# 425AK01A_S04.net
KiCad netlist of a schematic drawn in Altium Designer
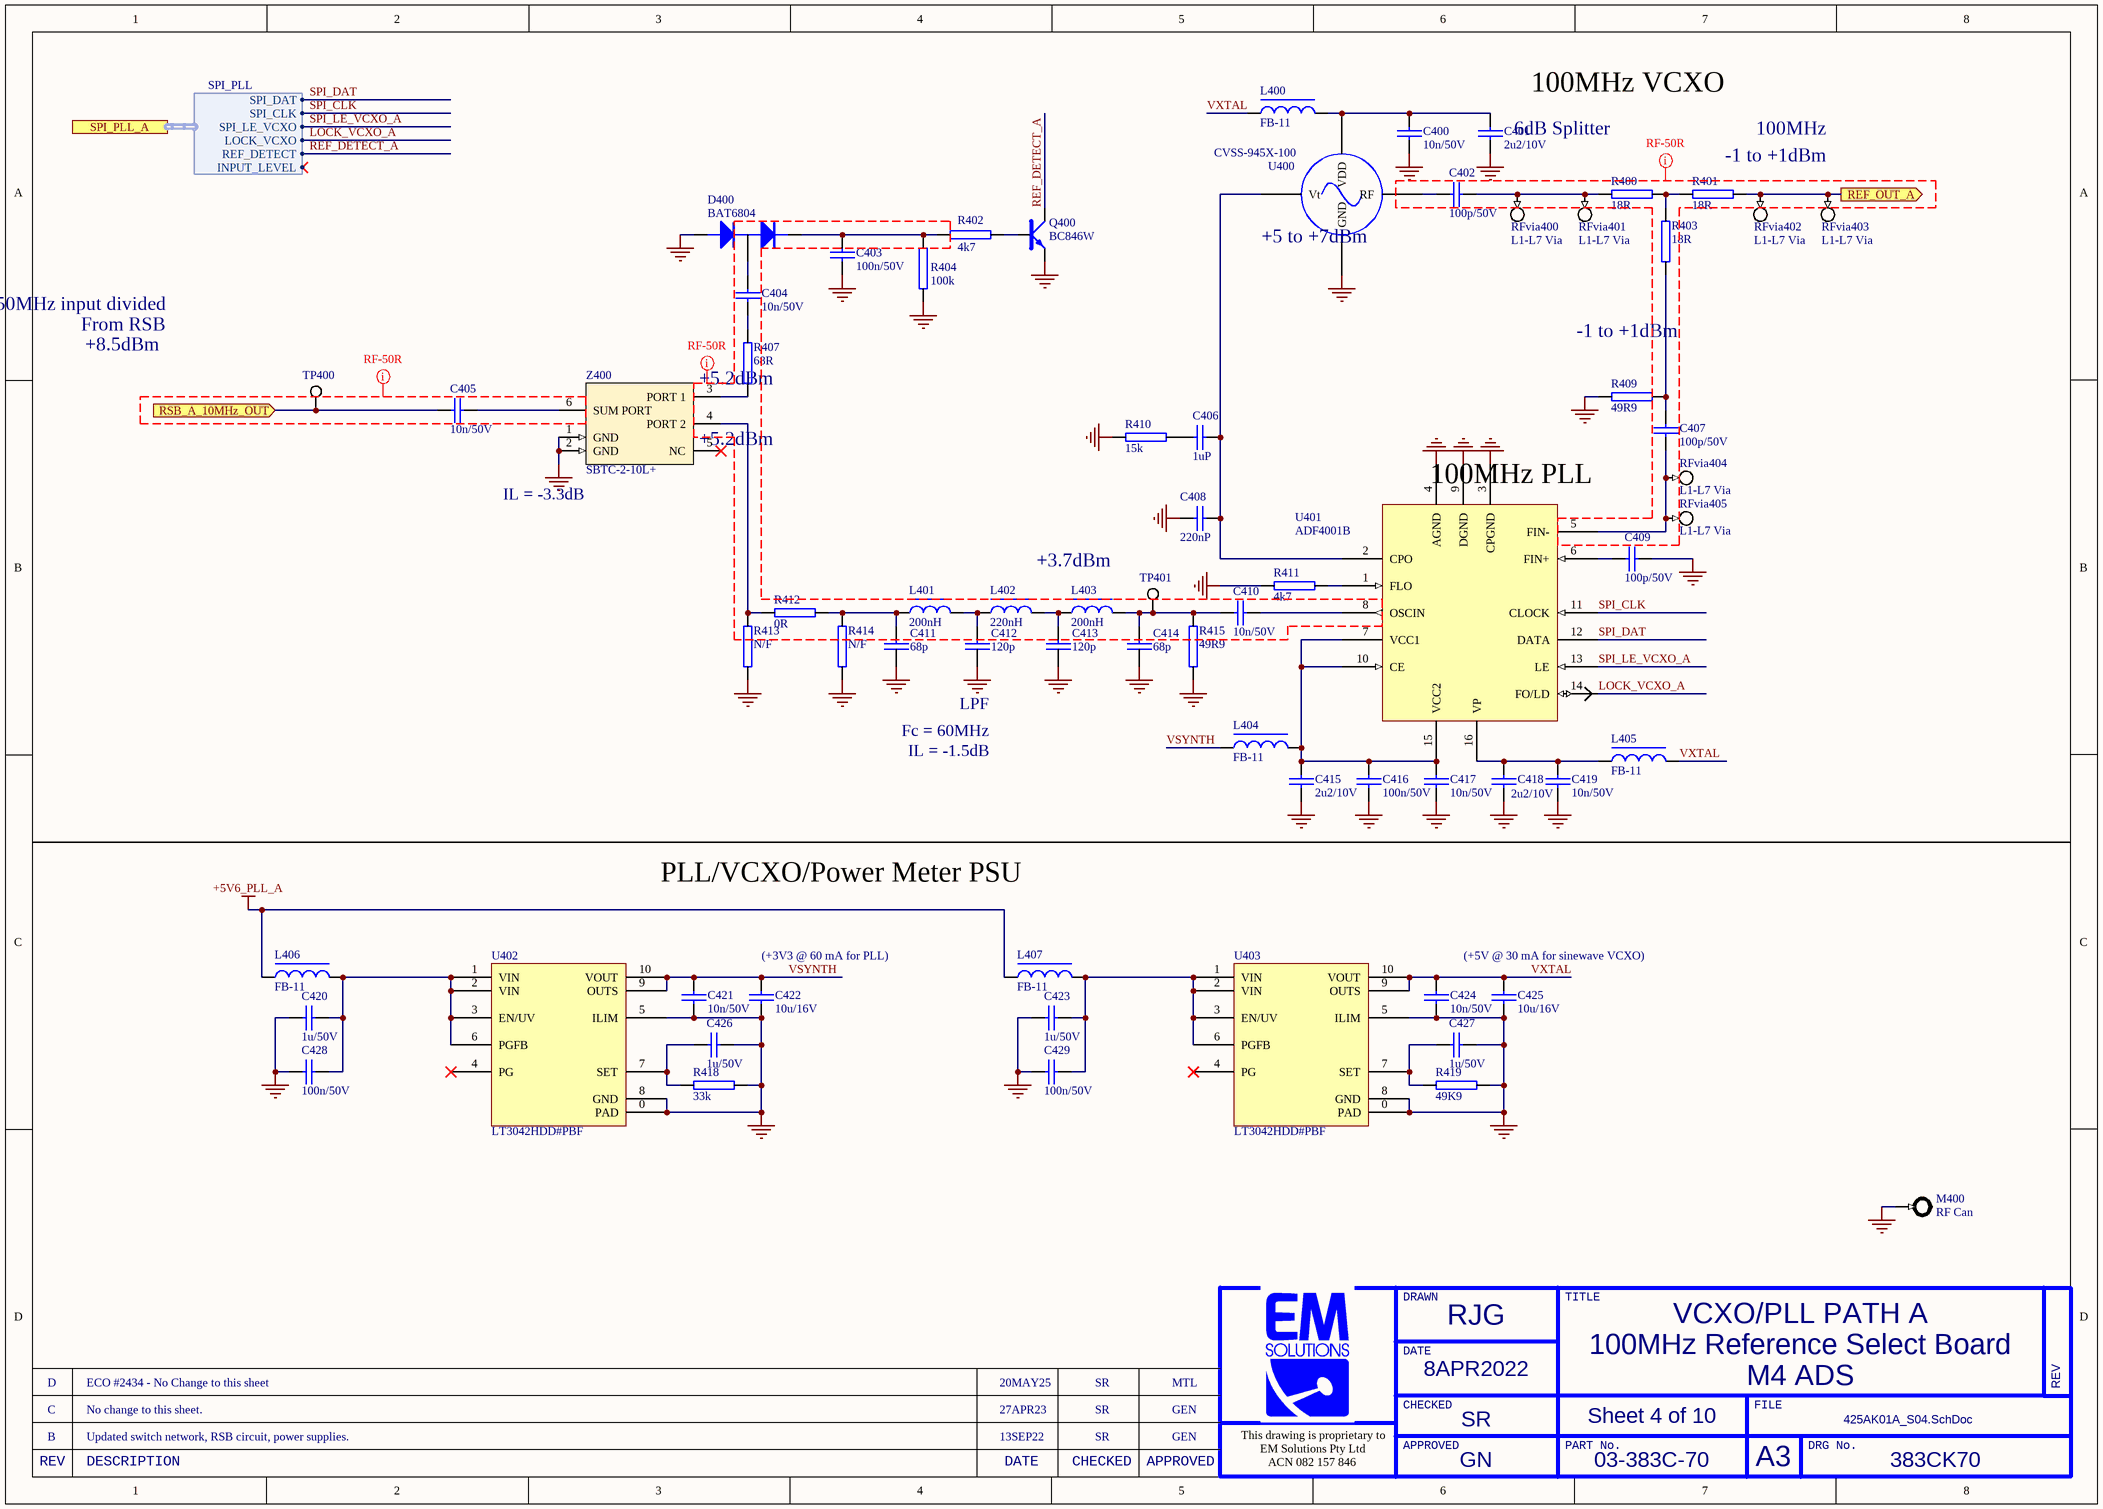
[diagram p0: 425AK01A_S04.SchDoc]

(export (version "E")
  (design (tool "Eeschema 10.0.6"))
  (components
    (comp (ref "C400")
      (value "10n/50V")
      (footprint "0402C")
      (description "Capacitor, 0402, 10n X7R 10% 50V Ceramic, NiSn")
      (fields (field (name "PART NUMBER") "41-010N-12") (field (name "MANUFACTURER") "MURATA"))
      (libsource (lib "EM DFM Library") (part "CAP"))
    )
    (comp (ref "C401")
      (value "2u2/10V")
      (footprint "0603C")
      (description "Capacitor, 0603, 2u2 X7R 10% 10V Ceramic, NiSn")
      (fields (field (name "PART NUMBER") "41-02U2-06") (field (name "MANUFACTURER") "MURATA"))
      (libsource (lib "EM DFM Library") (part "CAP"))
    )
    (comp (ref "C402")
      (value "100p/50V")
      (footprint "0402C")
      (description "Capacitor, 0402, 100p NPO 5% 50V Ceramic, AEC-Q200")
      (fields (field (name "PART NUMBER") "41-100P-11") (field (name "MANUFACTURER") "TDK"))
      (libsource (lib "EM DFM Library") (part "CAP"))
    )
    (comp (ref "C403")
      (value "100n/50V")
      (footprint "0402C")
      (description "Capacitor, 0402, 100n, X7R, 10% 50V, Ceramic")
      (fields (field (name "PART NUMBER") "41-100N-13") (field (name "MANUFACTURER") "MURATA"))
      (libsource (lib "EM DFM Library") (part "CAP"))
    )
    (comp (ref "C404")
      (value "10n/50V")
      (footprint "0402C")
      (description "Capacitor, 0402, 10n X7R 10% 50V Ceramic, NiSn")
      (fields (field (name "PART NUMBER") "41-010N-12") (field (name "MANUFACTURER") "MURATA"))
      (libsource (lib "EM DFM Library") (part "CAP"))
    )
    (comp (ref "C405")
      (value "10n/50V")
      (footprint "0402C")
      (description "Capacitor, 0402, 10n X7R 10% 50V Ceramic, NiSn")
      (fields (field (name "PART NUMBER") "41-010N-12") (field (name "MANUFACTURER") "MURATA"))
      (libsource (lib "EM DFM Library") (part "CAP"))
    )
    (comp (ref "C406")
      (value "1uP")
      (footprint "1210C")
      (description "Capacitor, 1210, 1u PPS 20% 16V Plastic Film")
      (fields (field (name "PART NUMBER") "41-01U0-05") (field (name "MANUFACTURER") "PANASONIC"))
      (libsource (lib "EM DFM Library") (part "CAP"))
    )
    (comp (ref "C407")
      (value "100p/50V")
      (footprint "0402C")
      (description "Capacitor, 0402, 100p NPO 5% 50V Ceramic, AEC-Q200")
      (fields (field (name "PART NUMBER") "41-100P-11") (field (name "MANUFACTURER") "TDK"))
      (libsource (lib "EM DFM Library") (part "CAP"))
    )
    (comp (ref "C408")
      (value "220nP")
      (footprint "1206C")
      (description "Capacitor, 1206, 220n PPS 20% 16V Plastic Film")
      (fields (field (name "PART NUMBER") "41-220N-05") (field (name "MANUFACTURER") "PANASONIC"))
      (libsource (lib "EM DFM Library") (part "CAP"))
    )
    (comp (ref "C409")
      (value "100p/50V")
      (footprint "0402C")
      (description "Capacitor, 0402, 100p NPO 5% 50V Ceramic, AEC-Q200")
      (fields (field (name "PART NUMBER") "41-100P-11") (field (name "MANUFACTURER") "TDK"))
      (libsource (lib "EM DFM Library") (part "CAP"))
    )
    (comp (ref "C410")
      (value "10n/50V")
      (footprint "0402C")
      (description "Capacitor, 0402, 10n X7R 10% 50V Ceramic, NiSn")
      (fields (field (name "PART NUMBER") "41-010N-12") (field (name "MANUFACTURER") "MURATA"))
      (libsource (lib "EM DFM Library") (part "CAP"))
    )
    (comp (ref "C411")
      (value "68p")
      (footprint "0402C")
      (description "Capacitor, 0402, 68p")
      (fields (field (name "PART NUMBER") "41-068P-08"))
      (libsource (lib "Russell") (part "41-068P-08"))
    )
    (comp (ref "C412")
      (value "120p")
      (footprint "0402C")
      (description "Capacitor, 0402, 120p NPO")
      (fields (field (name "PART NUMBER") "41-120P-05"))
      (libsource (lib "Russell") (part "41-120P-05"))
    )
    (comp (ref "C413")
      (value "120p")
      (footprint "0402C")
      (description "Capacitor, 0402, 120p NPO")
      (fields (field (name "PART NUMBER") "41-120P-05"))
      (libsource (lib "Russell") (part "41-120P-05"))
    )
    (comp (ref "C414")
      (value "68p")
      (footprint "0402C")
      (description "Capacitor, 0402, 68p")
      (fields (field (name "PART NUMBER") "41-068P-08"))
      (libsource (lib "Russell") (part "41-068P-08"))
    )
    (comp (ref "C415")
      (value "2u2/10V")
      (footprint "0603C")
      (description "Capacitor, 0603, 2u2 X7R 10% 10V Ceramic, NiSn")
      (fields (field (name "PART NUMBER") "41-02U2-06") (field (name "MANUFACTURER") "MURATA"))
      (libsource (lib "EM DFM Library") (part "CAP"))
    )
    (comp (ref "C416")
      (value "100n/50V")
      (footprint "0402C")
      (description "Capacitor, 0402, 100n, X7R, 10% 50V, Ceramic")
      (fields (field (name "PART NUMBER") "41-100N-13") (field (name "MANUFACTURER") "MURATA"))
      (libsource (lib "EM DFM Library") (part "CAP"))
    )
    (comp (ref "C417")
      (value "10n/50V")
      (footprint "0402C")
      (description "Capacitor, 0402, 10n X7R 10% 50V Ceramic, NiSn")
      (fields (field (name "PART NUMBER") "41-010N-12") (field (name "MANUFACTURER") "MURATA"))
      (libsource (lib "EM DFM Library") (part "CAP"))
    )
    (comp (ref "C418")
      (value "2u2/10V")
      (footprint "0603C")
      (description "Capacitor, 0603, 2u2 X7R 10% 10V Ceramic, NiSn")
      (fields (field (name "PART NUMBER") "41-02U2-06") (field (name "MANUFACTURER") "MURATA"))
      (libsource (lib "EM DFM Library") (part "CAP"))
    )
    (comp (ref "C419")
      (value "10n/50V")
      (footprint "0402C")
      (description "Capacitor, 0402, 10n X7R 10% 50V Ceramic, NiSn")
      (fields (field (name "PART NUMBER") "41-010N-12") (field (name "MANUFACTURER") "MURATA"))
      (libsource (lib "EM DFM Library") (part "CAP"))
    )
    (comp (ref "C420")
      (value "1u/50V")
      (footprint "0603C")
      (description "Capacitor, 0603, 1u X7R 10% 50V Ceramic, NiSn")
      (fields (field (name "PART NUMBER") "41-01U0-06") (field (name "MANUFACTURER") "TAIYOYUDEN"))
      (libsource (lib "EM DFM Library") (part "CAP"))
    )
    (comp (ref "C421")
      (value "10n/50V")
      (footprint "0402C")
      (description "Capacitor, 0402, 10n X7R 10% 50V Ceramic, NiSn")
      (fields (field (name "PART NUMBER") "41-010N-12") (field (name "MANUFACTURER") "MURATA"))
      (libsource (lib "EM DFM Library") (part "CAP"))
    )
    (comp (ref "C422")
      (value "10u/16V")
      (footprint "0805C")
      (description "Capacitor, 0805, 10u X7R 10% 16V Ceramic, NiSn")
      (fields (field (name "PART NUMBER") "41-010U-08") (field (name "MANUFACTURER") "SAMSUNG"))
      (libsource (lib "EM DFM Library") (part "CAP"))
    )
    (comp (ref "C423")
      (value "1u/50V")
      (footprint "0603C")
      (description "Capacitor, 0603, 1u X7R 10% 50V Ceramic, NiSn")
      (fields (field (name "PART NUMBER") "41-01U0-06") (field (name "MANUFACTURER") "TAIYOYUDEN"))
      (libsource (lib "EM DFM Library") (part "CAP"))
    )
    (comp (ref "C424")
      (value "10n/50V")
      (footprint "0402C")
      (description "Capacitor, 0402, 10n X7R 10% 50V Ceramic, NiSn")
      (fields (field (name "PART NUMBER") "41-010N-12") (field (name "MANUFACTURER") "MURATA"))
      (libsource (lib "EM DFM Library") (part "CAP"))
    )
    (comp (ref "C425")
      (value "10u/16V")
      (footprint "0805C")
      (description "Capacitor, 0805, 10u X7R 10% 16V Ceramic, NiSn")
      (fields (field (name "PART NUMBER") "41-010U-08") (field (name "MANUFACTURER") "SAMSUNG"))
      (libsource (lib "EM DFM Library") (part "CAP"))
    )
    (comp (ref "C426")
      (value "1u/50V")
      (footprint "0603C")
      (description "Capacitor, 0603, 1u X7R 10% 50V Ceramic, NiSn")
      (fields (field (name "PART NUMBER") "41-01U0-06") (field (name "MANUFACTURER") "TAIYOYUDEN"))
      (libsource (lib "EM DFM Library") (part "CAP"))
    )
    (comp (ref "C427")
      (value "1u/50V")
      (footprint "0603C")
      (description "Capacitor, 0603, 1u X7R 10% 50V Ceramic, NiSn")
      (fields (field (name "PART NUMBER") "41-01U0-06") (field (name "MANUFACTURER") "TAIYOYUDEN"))
      (libsource (lib "EM DFM Library") (part "CAP"))
    )
    (comp (ref "C428")
      (value "100n/50V")
      (footprint "0402C")
      (description "Capacitor, 0402, 100n, X7R, 10% 50V, Ceramic")
      (fields (field (name "PART NUMBER") "41-100N-13") (field (name "MANUFACTURER") "MURATA"))
      (libsource (lib "EM DFM Library") (part "CAP"))
    )
    (comp (ref "C429")
      (value "100n/50V")
      (footprint "0402C")
      (description "Capacitor, 0402, 100n, X7R, 10% 50V, Ceramic")
      (fields (field (name "PART NUMBER") "41-100N-13") (field (name "MANUFACTURER") "MURATA"))
      (libsource (lib "EM DFM Library") (part "CAP"))
    )
    (comp (ref "D400")
      (value "BAT6804")
      (footprint "SOT-23DAP")
      (description "*Diode, Schottky, Series Pair, 8V 130mA, SOT-23-3")
      (fields (field (name "PART NUMBER") "60-BAT68-04") (field (name "MANUFACTURER") "INFINEON"))
      (libsource (lib "EM DFM Library") (part "DIODE_AP2"))
    )
    (comp (ref "L400")
      (value "FB-11")
      (footprint "0402L")
      (description "Solid Inductor, 600ohm@100MHz, DCR=0.52, 0.3A, 0402 size")
      (fields (field (name "PART NUMBER") "46-B-11") (field (name "MANUFACTURER") "TDK"))
      (libsource (lib "EM DFM Library") (part "IND"))
    )
    (comp (ref "L401")
      (value "200nH")
      (footprint "0402L")
      (description "Inductor, Chip, 200nH, 0402")
      (fields (field (name "PART NUMBER") "46-200N-04"))
      (libsource (lib "Russell") (part "46-200N-04"))
    )
    (comp (ref "L402")
      (value "220nH")
      (footprint "0402L")
      (description "Inductor, Chip, 220nH, 0402")
      (fields (field (name "PART NUMBER") "46-220N-05"))
      (libsource (lib "Russell") (part "46-220N-05"))
    )
    (comp (ref "L403")
      (value "200nH")
      (footprint "0402L")
      (description "Inductor, Chip, 200nH, 0402")
      (fields (field (name "PART NUMBER") "46-200N-04"))
      (libsource (lib "Russell") (part "46-200N-04"))
    )
    (comp (ref "L404")
      (value "FB-11")
      (footprint "0402L")
      (description "Solid Inductor, 600ohm@100MHz, DCR=0.52, 0.3A, 0402 size")
      (fields (field (name "PART NUMBER") "46-B-11") (field (name "MANUFACTURER") "TDK"))
      (libsource (lib "EM DFM Library") (part "IND"))
    )
    (comp (ref "L405")
      (value "FB-11")
      (footprint "0402L")
      (description "Solid Inductor, 600ohm@100MHz, DCR=0.52, 0.3A, 0402 size")
      (fields (field (name "PART NUMBER") "46-B-11") (field (name "MANUFACTURER") "TDK"))
      (libsource (lib "EM DFM Library") (part "IND"))
    )
    (comp (ref "L406")
      (value "FB-11")
      (footprint "0402L")
      (description "Solid Inductor, 600ohm@100MHz, DCR=0.52, 0.3A, 0402 size")
      (fields (field (name "PART NUMBER") "46-B-11") (field (name "MANUFACTURER") "TDK"))
      (libsource (lib "") (part "IND_1"))
    )
    (comp (ref "L407")
      (value "FB-11")
      (footprint "0402L")
      (description "Solid Inductor, 600ohm@100MHz, DCR=0.52, 0.3A, 0402 size")
      (fields (field (name "PART NUMBER") "46-B-11") (field (name "MANUFACTURER") "TDK"))
      (libsource (lib "") (part "IND_1"))
    )
    (comp (ref "M400")
      (value "RF Can")
      (footprint "Can_38x25.4x6mm")
      (fields (field (name "PART NUMBER") "11-0256"))
      (libsource (lib "Russell") (part "Can-RF"))
    )
    (comp (ref "Q400")
      (value "BC846W")
      (footprint "SOT-323BJT")
      (description "Transistor, NPN Si, GenPur 65V 100mA, SOT-323")
      (fields (field (name "PART NUMBER") "62-BC846-01") (field (name "MANUFACTURER") "TAIWAN SEMI"))
      (libsource (lib "EM DFM Library") (part "NPN"))
    )
    (comp (ref "R400")
      (value "18R")
      (footprint "0402")
      (description "Resistor, 0402, 18R 1% 0.063W")
      (fields (field (name "PART NUMBER") "44-018R-10") (field (name "MANUFACTURER") "GENERIC"))
      (libsource (lib "EM DFM Library") (part "RES"))
    )
    (comp (ref "R401")
      (value "18R")
      (footprint "0402")
      (description "Resistor, 0402, 18R 1% 0.063W")
      (fields (field (name "PART NUMBER") "44-018R-10") (field (name "MANUFACTURER") "GENERIC"))
      (libsource (lib "EM DFM Library") (part "RES"))
    )
    (comp (ref "R402")
      (value "4k7")
      (footprint "0402")
      (description "Resistor, 0402, 4k7 1% 0.063W")
      (fields (field (name "PART NUMBER") "44-04K7-10") (field (name "MANUFACTURER") "PHILIPS"))
      (libsource (lib "EM DFM Library") (part "RES"))
    )
    (comp (ref "R403")
      (value "18R")
      (footprint "0402")
      (description "Resistor, 0402, 18R 1% 0.063W")
      (fields (field (name "PART NUMBER") "44-018R-10") (field (name "MANUFACTURER") "GENERIC"))
      (libsource (lib "EM DFM Library") (part "RES"))
    )
    (comp (ref "R404")
      (value "100k")
      (footprint "0402")
      (description "Resistor, 0402, 100k 1% 0.063W")
      (fields (field (name "PART NUMBER") "44-100K-10") (field (name "MANUFACTURER") "PHILIPS"))
      (libsource (lib "EM DFM Library") (part "RES"))
    )
    (comp (ref "R407")
      (value "68R")
      (footprint "0402")
      (description "Resistor, 0402, 68R 1% 0.063W")
      (fields (field (name "PART NUMBER") "44-068R-10") (field (name "MANUFACTURER") "PHILIPS"))
      (libsource (lib "EM DFM Library") (part "RES"))
    )
    (comp (ref "R409")
      (value "49R9")
      (footprint "0402")
      (description "Resistor, 0402, 49R9 1% 0.063W")
      (fields (field (name "PART NUMBER") "44-049R9-10") (field (name "MANUFACTURER") "YAGEO"))
      (libsource (lib "EM DFM Library") (part "RES"))
    )
    (comp (ref "R410")
      (value "15k")
      (footprint "0402")
      (description "Resistor, 0402, 15k 1% 0.063W")
      (fields (field (name "PART NUMBER") "44-015K-10") (field (name "MANUFACTURER") "PHILIPS"))
      (libsource (lib "EM DFM Library") (part "RES"))
    )
    (comp (ref "R411")
      (value "4k7")
      (footprint "0402")
      (description "Resistor, 0402, 4k7 1% 0.063W")
      (fields (field (name "PART NUMBER") "44-04K7-10") (field (name "MANUFACTURER") "PHILIPS"))
      (libsource (lib "EM DFM Library") (part "RES"))
    )
    (comp (ref "R412")
      (value "0R")
      (footprint "0402")
      (description "Resistor, 0402, 0R 1% 0.063W")
      (fields (field (name "PART NUMBER") "44-000R-10") (field (name "MANUFACTURER") "GENERIC"))
      (libsource (lib "EM DFM Library") (part "RES"))
    )
    (comp (ref "R413")
      (value "N/F")
      (footprint "0402")
      (description "Resistor, 0402, SOT, Not Fitted")
      (fields (field (name "PART NUMBER") "44-N/F-10"))
      (libsource (lib "EM DFM Library") (part "RES"))
    )
    (comp (ref "R414")
      (value "N/F")
      (footprint "0402")
      (description "Resistor, 0402, SOT, Not Fitted")
      (fields (field (name "PART NUMBER") "44-N/F-10"))
      (libsource (lib "EM DFM Library") (part "RES"))
    )
    (comp (ref "R415")
      (value "49R9")
      (footprint "0402")
      (description "Resistor, 0402, 49R9 1% 0.063W")
      (fields (field (name "PART NUMBER") "44-049R9-10") (field (name "MANUFACTURER") "YAGEO"))
      (libsource (lib "EM DFM Library") (part "RES"))
    )
    (comp (ref "R418")
      (value "33k")
      (footprint "0402")
      (description "Resistor, 0402, 33k 1% 0.063W")
      (fields (field (name "PART NUMBER") "44-033K-10") (field (name "MANUFACTURER") "PHILIPS"))
      (libsource (lib "EM DFM Library") (part "RES"))
    )
    (comp (ref "R419")
      (value "49K9")
      (footprint "0402")
      (description "Resistor, 0402, 49.9K, 1%, 0.1W, ThickFilm, AEC-Q200")
      (fields (field (name "PART NUMBER") "44-49K9-01") (field (name "MANUFACTURER") "PANASONIC"))
      (libsource (lib "EM DFM Library") (part "RES"))
    )
    (comp (ref "RFvia400")
      (value "L1-L7 Via")
      (footprint "RFvia_L1-L7")
      (description "RF Via from layer 1 to layer 7, on an 8-layer board.")
      (libsource (lib "RFvias-8layer") (part "RFvia_L1-L7"))
    )
    (comp (ref "RFvia401")
      (value "L1-L7 Via")
      (footprint "RFvia_L1-L7")
      (description "RF Via from layer 1 to layer 7, on an 8-layer board.")
      (libsource (lib "RFvias-8layer") (part "RFvia_L1-L7"))
    )
    (comp (ref "RFvia402")
      (value "L1-L7 Via")
      (footprint "RFvia_L1-L7")
      (description "RF Via from layer 1 to layer 7, on an 8-layer board.")
      (libsource (lib "RFvias-8layer") (part "RFvia_L1-L7"))
    )
    (comp (ref "RFvia403")
      (value "L1-L7 Via")
      (footprint "RFvia_L1-L7")
      (description "RF Via from layer 1 to layer 7, on an 8-layer board.")
      (libsource (lib "RFvias-8layer") (part "RFvia_L1-L7"))
    )
    (comp (ref "RFvia404")
      (value "L1-L7 Via")
      (footprint "RFvia_L1-L7")
      (description "RF Via from layer 1 to layer 7, on an 8-layer board.")
      (libsource (lib "RFvias-8layer") (part "RFvia_L1-L7"))
    )
    (comp (ref "RFvia405")
      (value "L1-L7 Via")
      (footprint "RFvia_L1-L7")
      (description "RF Via from layer 1 to layer 7, on an 8-layer board.")
      (libsource (lib "RFvias-8layer") (part "RFvia_L1-L7"))
    )
    (comp (ref "TP400")
      (value "Pad")
      (footprint "Testpoint-0.5mm-SMT-withPaste")
      (description "Pad that can be a test point or a hot via")
      (libsource (lib "Russell") (part "Pad"))
    )
    (comp (ref "TP401")
      (value "Pad")
      (footprint "Testpoint-0.5mm-SMT-withPaste")
      (description "Pad that can be a test point or a hot via")
      (libsource (lib "Russell") (part "Pad"))
    )
    (comp (ref "U400")
      (value "CVSS-945X-100")
      (footprint "CVHD-950")
      (description "VCXO, 100.00MHz, Sine 5V, SMD")
      (fields (field (name "PART NUMBER") "35-0223") (field (name "MANUFACTURER") "CRYSTEK"))
      (libsource (lib "EM DFM Library") (part "CVHD-950X-100"))
    )
    (comp (ref "U401")
      (value "ADF4001B")
      (footprint "TSSOP-16")
      (description "PLL Clock Gen, 200MHz, Serial TSSOP-16")
      (fields (field (name "PART NUMBER") "54-4001-01") (field (name "MANUFACTURER") "ANLG DEV"))
      (libsource (lib "EM DFM Library") (part "ADF4001BRUZ"))
    )
    (comp (ref "U402")
      (value "LT3042HDD#PBF")
      (footprint "DFN50P300X300X80_HS-11N")
      (description "Volt Regulator, Vin=1.8-20V, Vin=0-15V, 200mA, Low Noise, -40to+125C")
      (fields (field (name "PART NUMBER") "52-3042-01") (field (name "MANUFACTURER") "ANLG DEV"))
      (libsource (lib "EM DFM Library") (part "LT3042"))
    )
    (comp (ref "U403")
      (value "LT3042HDD#PBF")
      (footprint "DFN50P300X300X80_HS-11N")
      (description "Volt Regulator, Vin=1.8-20V, Vin=0-15V, 200mA, Low Noise, -40to+125C")
      (fields (field (name "PART NUMBER") "52-3042-01") (field (name "MANUFACTURER") "ANLG DEV"))
      (libsource (lib "EM DFM Library") (part "LT3042"))
    )
    (comp (ref "Z400")
      (value "SBTC-2-10L+")
      (footprint "SBTC-2-10L+")
      (description "Divider/Combiner, 2 Way, 0 deg, 10 -1000MHz, Tx Line Tranformer")
      (fields (field (name "PART NUMBER") "33-0055") (field (name "MANUFACTURER") "MINICCTS"))
      (libsource (lib "EM DFM Library") (part "SBTC-2-10L+"))
    )
  )
  (nets
    (net (code "2") (name "+5V6_PLL_A") (class "Default")
      (node (ref "L406") (pin "2") (pinfunction "2_2") (pintype "passive"))
      (node (ref "L407") (pin "2") (pinfunction "2_2") (pintype "passive"))
    )
    (net (code "3") (name "/LOCK_VCXO_A") (class "Default")
      (node (ref "U401") (pin "14") (pinfunction "FO/LD_14") (pintype "bidirectional"))
    )
    (net (code "4") (name "/REF_DETECT_A") (class "Default")
      (node (ref "Q400") (pin "C") (pinfunction "C_C") (pintype "passive"))
    )
    (net (code "5") (name "/REF_OUT_A") (class "Default")
      (node (ref "R401") (pin "2") (pintype "passive"))
      (node (ref "RFvia402") (pin "1") (pinfunction "1_1") (pintype "input"))
      (node (ref "RFvia403") (pin "1") (pinfunction "1_1") (pintype "input"))
    )
    (net (code "6") (name "/RSB_A_10MHz_OUT") (class "Default")
      (node (ref "C405") (pin "1") (pintype "passive"))
      (node (ref "TP400") (pin "1") (pinfunction "1_1") (pintype "passive"))
    )
    (net (code "7") (name "/SPI_CLK") (class "Default")
      (node (ref "U401") (pin "11") (pinfunction "CLOCK_11") (pintype "input"))
    )
    (net (code "8") (name "/SPI_DAT") (class "Default")
      (node (ref "U401") (pin "12") (pinfunction "DATA_12") (pintype "passive"))
    )
    (net (code "9") (name "/SPI_LE_VCXO_A") (class "Default")
      (node (ref "U401") (pin "13") (pinfunction "LE_13") (pintype "input"))
    )
    (net (code "10") (name "/VSYNTH") (class "Default")
      (node (ref "C421") (pin "2") (pintype "passive"))
      (node (ref "C422") (pin "1") (pintype "passive"))
      (node (ref "L404") (pin "1") (pinfunction "1_1") (pintype "passive"))
      (node (ref "U402") (pin "10") (pinfunction "VOUT_10") (pintype "passive"))
      (node (ref "U402") (pin "9") (pinfunction "OUTS_9") (pintype "passive"))
    )
    (net (code "11") (name "/VXTAL") (class "Default")
      (node (ref "C424") (pin "2") (pintype "passive"))
      (node (ref "C425") (pin "1") (pintype "passive"))
      (node (ref "L400") (pin "1") (pinfunction "1_1") (pintype "passive"))
      (node (ref "L405") (pin "2") (pinfunction "2_2") (pintype "passive"))
      (node (ref "U403") (pin "10") (pinfunction "VOUT_10") (pintype "passive"))
      (node (ref "U403") (pin "9") (pinfunction "OUTS_9") (pintype "passive"))
    )
    (net (code "13") (name "GND") (class "Default")
      (node (ref "C400") (pin "2") (pintype "passive"))
      (node (ref "C401") (pin "2") (pintype "passive"))
      (node (ref "C403") (pin "1") (pintype "passive"))
      (node (ref "C408") (pin "1") (pintype "passive"))
      (node (ref "C409") (pin "2") (pintype "passive"))
      (node (ref "C411") (pin "1") (pintype "passive"))
      (node (ref "C412") (pin "1") (pintype "passive"))
      (node (ref "C413") (pin "1") (pintype "passive"))
      (node (ref "C414") (pin "1") (pintype "passive"))
      (node (ref "C415") (pin "2") (pintype "passive"))
      (node (ref "C416") (pin "2") (pintype "passive"))
      (node (ref "C417") (pin "2") (pintype "passive"))
      (node (ref "C418") (pin "2") (pintype "passive"))
      (node (ref "C419") (pin "2") (pintype "passive"))
      (node (ref "C420") (pin "1") (pintype "passive"))
      (node (ref "C421") (pin "1") (pintype "passive"))
      (node (ref "C422") (pin "2") (pintype "passive"))
      (node (ref "C423") (pin "1") (pintype "passive"))
      (node (ref "C424") (pin "1") (pintype "passive"))
      (node (ref "C425") (pin "2") (pintype "passive"))
      (node (ref "C426") (pin "2") (pintype "passive"))
      (node (ref "C427") (pin "2") (pintype "passive"))
      (node (ref "C428") (pin "2") (pintype "passive"))
      (node (ref "C429") (pin "2") (pintype "passive"))
      (node (ref "D400") (pin "A") (pintype "passive"))
      (node (ref "M400") (pin "0") (pinfunction "0_0") (pintype "input"))
      (node (ref "Q400") (pin "E") (pinfunction "E_E") (pintype "passive"))
      (node (ref "R404") (pin "1") (pintype "passive"))
      (node (ref "R409") (pin "2") (pintype "passive"))
      (node (ref "R410") (pin "2") (pintype "passive"))
      (node (ref "R411") (pin "1") (pintype "passive"))
      (node (ref "R413") (pin "1") (pintype "passive"))
      (node (ref "R414") (pin "1") (pintype "passive"))
      (node (ref "R415") (pin "1") (pintype "passive"))
      (node (ref "R418") (pin "1") (pintype "passive"))
      (node (ref "R419") (pin "1") (pintype "passive"))
      (node (ref "U400") (pin "2") (pinfunction "GND_2") (pintype "passive"))
      (node (ref "U401") (pin "3") (pinfunction "CPGND_3") (pintype "passive"))
      (node (ref "U401") (pin "4") (pinfunction "AGND_4") (pintype "passive"))
      (node (ref "U401") (pin "9") (pinfunction "DGND_9") (pintype "passive"))
      (node (ref "U402") (pin "0") (pinfunction "PAD_0") (pintype "passive"))
      (node (ref "U402") (pin "5") (pinfunction "ILIM_5") (pintype "passive"))
      (node (ref "U402") (pin "8") (pinfunction "GND_8") (pintype "passive"))
      (node (ref "U403") (pin "0") (pinfunction "PAD_0") (pintype "passive"))
      (node (ref "U403") (pin "5") (pinfunction "ILIM_5") (pintype "passive"))
      (node (ref "U403") (pin "8") (pinfunction "GND_8") (pintype "passive"))
      (node (ref "Z400") (pin "1") (pinfunction "GND_1") (pintype "input"))
      (node (ref "Z400") (pin "2") (pinfunction "GND_2") (pintype "input"))
    )
    (net (code "14") (name "Net-(C402-Pad1)") (class "Default")
      (node (ref "C402") (pin "1") (pintype "passive"))
      (node (ref "R400") (pin "1") (pintype "passive"))
      (node (ref "RFvia400") (pin "1") (pinfunction "1_1") (pintype "input"))
      (node (ref "RFvia401") (pin "1") (pinfunction "1_1") (pintype "input"))
    )
    (net (code "15") (name "Net-(C403-Pad2)") (class "Default")
      (node (ref "C403") (pin "2") (pintype "passive"))
      (node (ref "D400") (pin "K") (pintype "passive"))
      (node (ref "R402") (pin "2") (pintype "passive"))
      (node (ref "R404") (pin "2") (pintype "passive"))
    )
    (net (code "16") (name "Net-(C404-Pad1)") (class "Default")
      (node (ref "C404") (pin "1") (pintype "passive"))
      (node (ref "R407") (pin "2") (pintype "passive"))
    )
    (net (code "17") (name "Net-(C404-Pad2)") (class "Default")
      (node (ref "C404") (pin "2") (pintype "passive"))
      (node (ref "D400") (pin "KA") (pintype "passive"))
    )
    (net (code "18") (name "Net-(C406-Pad2)") (class "Default")
      (node (ref "C406") (pin "2") (pintype "passive"))
      (node (ref "R410") (pin "1") (pintype "passive"))
    )
    (net (code "19") (name "Net-(C407-Pad1)") (class "Default")
      (node (ref "C407") (pin "1") (pintype "passive"))
      (node (ref "R403") (pin "2") (pintype "passive"))
      (node (ref "R409") (pin "1") (pintype "passive"))
    )
    (net (code "20") (name "Net-(C410-Pad1)") (class "Default")
      (node (ref "C410") (pin "1") (pintype "passive"))
      (node (ref "C414") (pin "2") (pintype "passive"))
      (node (ref "L403") (pin "2") (pinfunction "2_2") (pintype "passive"))
      (node (ref "R415") (pin "2") (pintype "passive"))
      (node (ref "TP401") (pin "1") (pinfunction "1_1") (pintype "passive"))
    )
    (net (code "21") (name "Net-(C411-Pad2)") (class "Default")
      (node (ref "C411") (pin "2") (pintype "passive"))
      (node (ref "L401") (pin "1") (pinfunction "1_1") (pintype "passive"))
      (node (ref "R412") (pin "1") (pintype "passive"))
      (node (ref "R414") (pin "2") (pintype "passive"))
    )
    (net (code "22") (name "Net-(C412-Pad2)") (class "Default")
      (node (ref "C412") (pin "2") (pintype "passive"))
      (node (ref "L401") (pin "2") (pinfunction "2_2") (pintype "passive"))
      (node (ref "L402") (pin "1") (pinfunction "1_1") (pintype "passive"))
    )
    (net (code "23") (name "Net-(C413-Pad2)") (class "Default")
      (node (ref "C413") (pin "2") (pintype "passive"))
      (node (ref "L402") (pin "2") (pinfunction "2_2") (pintype "passive"))
      (node (ref "L403") (pin "1") (pinfunction "1_1") (pintype "passive"))
    )
    (net (code "24") (name "Net-(Q400-PadB)") (class "Default")
      (node (ref "Q400") (pin "B") (pinfunction "B_B") (pintype "passive"))
      (node (ref "R402") (pin "1") (pintype "passive"))
    )
    (net (code "25") (name "Net-(R400-Pad2)") (class "Default")
      (node (ref "R400") (pin "2") (pintype "passive"))
      (node (ref "R401") (pin "1") (pintype "passive"))
      (node (ref "R403") (pin "1") (pintype "passive"))
    )
    (net (code "26") (name "Net-(U400-RF)") (class "Default")
      (node (ref "C402") (pin "2") (pintype "passive"))
      (node (ref "U400") (pin "3") (pinfunction "RF_3") (pintype "passive"))
    )
    (net (code "27") (name "Net-(U400-VDD)") (class "Default")
      (node (ref "C400") (pin "1") (pintype "passive"))
      (node (ref "C401") (pin "1") (pintype "passive"))
      (node (ref "L400") (pin "2") (pinfunction "2_2") (pintype "passive"))
      (node (ref "U400") (pin "4") (pinfunction "VDD_4") (pintype "passive"))
    )
    (net (code "28") (name "Net-(U400-Vt)") (class "Default")
      (node (ref "C406") (pin "1") (pintype "passive"))
      (node (ref "C408") (pin "2") (pintype "passive"))
      (node (ref "U400") (pin "1") (pinfunction "Vt_1") (pintype "passive"))
      (node (ref "U401") (pin "2") (pinfunction "CPO_2") (pintype "passive"))
    )
    (net (code "29") (name "Net-(U401-CE)") (class "Default")
      (node (ref "C415") (pin "1") (pintype "passive"))
      (node (ref "C416") (pin "1") (pintype "passive"))
      (node (ref "C417") (pin "1") (pintype "passive"))
      (node (ref "L404") (pin "2") (pinfunction "2_2") (pintype "passive"))
      (node (ref "U401") (pin "10") (pinfunction "CE_10") (pintype "input"))
      (node (ref "U401") (pin "15") (pinfunction "VCC2_15") (pintype "power_in"))
      (node (ref "U401") (pin "7") (pinfunction "VCC1_7") (pintype "power_in"))
    )
    (net (code "30") (name "Net-(U401-FIN+)") (class "Default")
      (node (ref "C409") (pin "1") (pintype "passive"))
      (node (ref "U401") (pin "6") (pinfunction "FIN+_6") (pintype "input"))
    )
    (net (code "31") (name "Net-(U401-FIN-)") (class "Default")
      (node (ref "C407") (pin "2") (pintype "passive"))
      (node (ref "RFvia404") (pin "1") (pinfunction "1_1") (pintype "input"))
      (node (ref "RFvia405") (pin "1") (pinfunction "1_1") (pintype "input"))
      (node (ref "U401") (pin "5") (pinfunction "FIN-_5") (pintype "power_in"))
    )
    (net (code "32") (name "Net-(U401-FLO)") (class "Default")
      (node (ref "R411") (pin "2") (pintype "passive"))
      (node (ref "U401") (pin "1") (pinfunction "FLO_1") (pintype "input"))
    )
    (net (code "33") (name "Net-(U401-OSCIN)") (class "Default")
      (node (ref "C410") (pin "2") (pintype "passive"))
      (node (ref "U401") (pin "8") (pinfunction "OSCIN_8") (pintype "output"))
    )
    (net (code "34") (name "Net-(U401-VP)") (class "Default")
      (node (ref "C418") (pin "1") (pintype "passive"))
      (node (ref "C419") (pin "1") (pintype "passive"))
      (node (ref "L405") (pin "1") (pinfunction "1_1") (pintype "passive"))
      (node (ref "U401") (pin "16") (pinfunction "VP_16") (pintype "power_in"))
    )
    (net (code "35") (name "Net-(U402-EN{slash}UV)") (class "Default")
      (node (ref "C420") (pin "2") (pintype "passive"))
      (node (ref "C428") (pin "1") (pintype "passive"))
      (node (ref "L406") (pin "1") (pinfunction "1_1") (pintype "passive"))
      (node (ref "U402") (pin "1") (pinfunction "VIN_1") (pintype "passive"))
      (node (ref "U402") (pin "2") (pinfunction "VIN_2") (pintype "passive"))
      (node (ref "U402") (pin "3") (pinfunction "EN/UV_3") (pintype "passive"))
      (node (ref "U402") (pin "6") (pinfunction "PGFB_6") (pintype "passive"))
    )
    (net (code "36") (name "Net-(U402-SET)") (class "Default")
      (node (ref "C426") (pin "1") (pintype "passive"))
      (node (ref "R418") (pin "2") (pintype "passive"))
      (node (ref "U402") (pin "7") (pinfunction "SET_7") (pintype "passive"))
    )
    (net (code "37") (name "Net-(U403-EN{slash}UV)") (class "Default")
      (node (ref "C423") (pin "2") (pintype "passive"))
      (node (ref "C429") (pin "1") (pintype "passive"))
      (node (ref "L407") (pin "1") (pinfunction "1_1") (pintype "passive"))
      (node (ref "U403") (pin "1") (pinfunction "VIN_1") (pintype "passive"))
      (node (ref "U403") (pin "2") (pinfunction "VIN_2") (pintype "passive"))
      (node (ref "U403") (pin "3") (pinfunction "EN/UV_3") (pintype "passive"))
      (node (ref "U403") (pin "6") (pinfunction "PGFB_6") (pintype "passive"))
    )
    (net (code "38") (name "Net-(U403-SET)") (class "Default")
      (node (ref "C427") (pin "1") (pintype "passive"))
      (node (ref "R419") (pin "2") (pintype "passive"))
      (node (ref "U403") (pin "7") (pinfunction "SET_7") (pintype "passive"))
    )
    (net (code "39") (name "Net-(Z400-PORT_1)") (class "Default")
      (node (ref "R407") (pin "1") (pintype "passive"))
      (node (ref "Z400") (pin "3") (pinfunction "PORT_1_3") (pintype "passive"))
    )
    (net (code "40") (name "Net-(Z400-PORT_2)") (class "Default")
      (node (ref "R412") (pin "2") (pintype "passive"))
      (node (ref "R413") (pin "2") (pintype "passive"))
      (node (ref "Z400") (pin "4") (pinfunction "PORT_2_4") (pintype "passive"))
    )
    (net (code "41") (name "Net-(Z400-SUM_PORT)") (class "Default")
      (node (ref "C405") (pin "2") (pintype "passive"))
      (node (ref "Z400") (pin "6") (pinfunction "SUM_PORT_6") (pintype "passive"))
    )
    (net (code "42") (name "unconnected-(U402-PG-Pad4)") (class "Default")
      (node (ref "U402") (pin "4") (pinfunction "PG_4") (pintype "passive+no_connect"))
    )
    (net (code "43") (name "unconnected-(U403-PG-Pad4)") (class "Default")
      (node (ref "U403") (pin "4") (pinfunction "PG_4") (pintype "passive+no_connect"))
    )
    (net (code "44") (name "unconnected-(Z400-NC-Pad5)") (class "Default")
      (node (ref "Z400") (pin "5") (pinfunction "NC_5") (pintype "passive+no_connect"))
    )
  )
)
